# ACC_ICM20948.net
KiCad netlist of a schematic drawn in Altium Designer
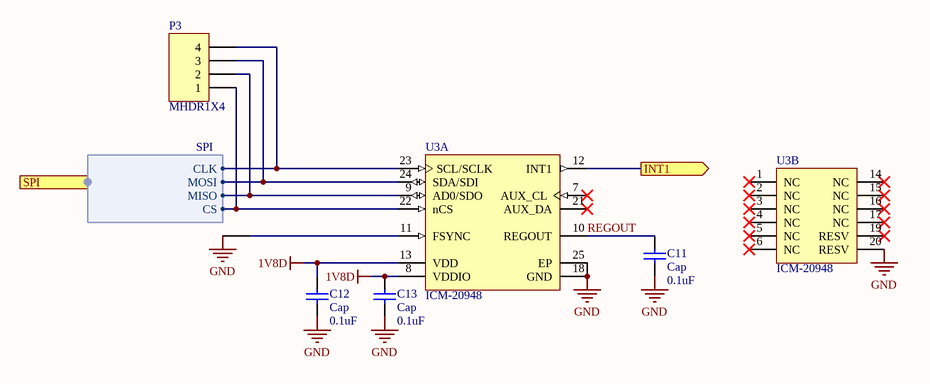
[diagram p0: ACC_ICM20948.SchDoc]

(export (version "E")
  (design (tool "Eeschema 10.0.6"))
  (components
    (comp (ref "C11")
      (value "Cap")
      (footprint "CAPC1005N")
      (description "Capacitor")
      (fields (field (name "ALTIUM_VALUE") "0.1uF") (field (name "PUBLISHER") "Altium Limited"))
      (libsource (lib "Miscellaneous Devices") (part "Cap"))
    )
    (comp (ref "C12")
      (value "Cap")
      (footprint "CAPC1005N")
      (description "Capacitor")
      (fields (field (name "ALTIUM_VALUE") "0.1uF") (field (name "PUBLISHER") "Altium Limited"))
      (libsource (lib "Miscellaneous Devices") (part "Cap"))
    )
    (comp (ref "C13")
      (value "Cap")
      (footprint "CAPC1005N")
      (description "Capacitor")
      (fields (field (name "ALTIUM_VALUE") "0.1uF") (field (name "PUBLISHER") "Altium Limited"))
      (libsource (lib "Miscellaneous Devices") (part "Cap"))
    )
    (comp (ref "P3")
      (value "MHDR1X4")
      (footprint "MHDR1X4")
      (description "Header, 4-Pin")
      (fields (field (name "PUBLISHER") "Altium Limited"))
      (libsource (lib "Miscellaneous Connectors") (part "MHDR1X4"))
    )
    (comp (ref "U3")
      (value "ICM-20948")
      (footprint "TDK-QFN-24_M")
      (fields (field (name "MANUFACTURER") "TDK"))
      (libsource (lib "Altium Content Vault") (part "TDK-ICM-20948-QFN-24"))
    )
  )
  (nets
    (net (code "2") (name "/INT1") (class "Default")
      (node (ref "U3") (pin "12") (pinfunction "INT1_12") (pintype "output"))
    )
    (net (code "3") (name "/REGOUT") (class "Default")
      (node (ref "C11") (pin "2") (pinfunction "2_2") (pintype "passive"))
      (node (ref "U3") (pin "10") (pinfunction "REGOUT_10") (pintype "passive"))
    )
    (net (code "5") (name "1V8D") (class "Default")
      (node (ref "C12") (pin "2") (pinfunction "2_2") (pintype "passive"))
      (node (ref "C13") (pin "2") (pinfunction "2_2") (pintype "passive"))
      (node (ref "U3") (pin "13") (pinfunction "VDD_13") (pintype "power_in"))
      (node (ref "U3") (pin "8") (pinfunction "VDDIO_8") (pintype "power_in"))
    )
    (net (code "6") (name "GND") (class "Default")
      (node (ref "C11") (pin "1") (pinfunction "1_1") (pintype "passive"))
      (node (ref "C12") (pin "1") (pinfunction "1_1") (pintype "passive"))
      (node (ref "C13") (pin "1") (pinfunction "1_1") (pintype "passive"))
      (node (ref "U3") (pin "11") (pinfunction "FSYNC_11") (pintype "input"))
      (node (ref "U3") (pin "18") (pinfunction "GND_18") (pintype "power_in"))
      (node (ref "U3") (pin "20") (pinfunction "RESV_20") (pintype "passive"))
      (node (ref "U3") (pin "25") (pinfunction "EP_25") (pintype "passive"))
    )
    (net (code "7") (name "Net-(U3A-AD0{slash}SDO)") (class "Default")
      (node (ref "P3") (pin "2") (pinfunction "2_2") (pintype "passive"))
      (node (ref "U3") (pin "9") (pinfunction "AD0/SDO_9") (pintype "bidirectional"))
    )
    (net (code "8") (name "Net-(U3A-SCL{slash}SCLK)") (class "Default")
      (node (ref "P3") (pin "4") (pinfunction "4_4") (pintype "passive"))
      (node (ref "U3") (pin "23") (pinfunction "SCL/SCLK_23") (pintype "input"))
    )
    (net (code "9") (name "Net-(U3A-SDA{slash}SDI)") (class "Default")
      (node (ref "P3") (pin "3") (pinfunction "3_3") (pintype "passive"))
      (node (ref "U3") (pin "24") (pinfunction "SDA/SDI_24") (pintype "bidirectional"))
    )
    (net (code "10") (name "Net-(U3A-nCS)") (class "Default")
      (node (ref "P3") (pin "1") (pinfunction "1_1") (pintype "passive"))
      (node (ref "U3") (pin "22") (pinfunction "nCS_22") (pintype "input"))
    )
    (net (code "11") (name "unconnected-(U3A-AUX_CL-Pad7)") (class "Default")
      (node (ref "U3") (pin "7") (pinfunction "AUX_CL_7") (pintype "input+no_connect"))
    )
    (net (code "12") (name "unconnected-(U3A-AUX_DA-Pad21)") (class "Default")
      (node (ref "U3") (pin "21") (pinfunction "AUX_DA_21") (pintype "passive+no_connect"))
    )
    (net (code "13") (name "unconnected-(U3B-NC-Pad1)") (class "Default")
      (node (ref "U3") (pin "1") (pinfunction "NC_1") (pintype "passive+no_connect"))
    )
    (net (code "14") (name "unconnected-(U3B-NC-Pad2)") (class "Default")
      (node (ref "U3") (pin "2") (pinfunction "NC_2") (pintype "passive+no_connect"))
    )
    (net (code "15") (name "unconnected-(U3B-NC-Pad3)") (class "Default")
      (node (ref "U3") (pin "3") (pinfunction "NC_3") (pintype "passive+no_connect"))
    )
    (net (code "16") (name "unconnected-(U3B-NC-Pad4)") (class "Default")
      (node (ref "U3") (pin "4") (pinfunction "NC_4") (pintype "passive+no_connect"))
    )
    (net (code "17") (name "unconnected-(U3B-NC-Pad5)") (class "Default")
      (node (ref "U3") (pin "5") (pinfunction "NC_5") (pintype "passive+no_connect"))
    )
    (net (code "18") (name "unconnected-(U3B-NC-Pad6)") (class "Default")
      (node (ref "U3") (pin "6") (pinfunction "NC_6") (pintype "passive+no_connect"))
    )
    (net (code "19") (name "unconnected-(U3B-NC-Pad14)") (class "Default")
      (node (ref "U3") (pin "14") (pinfunction "NC_14") (pintype "passive+no_connect"))
    )
    (net (code "20") (name "unconnected-(U3B-NC-Pad15)") (class "Default")
      (node (ref "U3") (pin "15") (pinfunction "NC_15") (pintype "passive+no_connect"))
    )
    (net (code "21") (name "unconnected-(U3B-NC-Pad16)") (class "Default")
      (node (ref "U3") (pin "16") (pinfunction "NC_16") (pintype "passive+no_connect"))
    )
    (net (code "22") (name "unconnected-(U3B-NC-Pad17)") (class "Default")
      (node (ref "U3") (pin "17") (pinfunction "NC_17") (pintype "passive+no_connect"))
    )
    (net (code "23") (name "unconnected-(U3B-RESV-Pad19)") (class "Default")
      (node (ref "U3") (pin "19") (pinfunction "RESV_19") (pintype "passive+no_connect"))
    )
  )
)
